# ADC-POWER_SUPPLY_2.net
KiCad netlist of a schematic drawn in Altium Designer
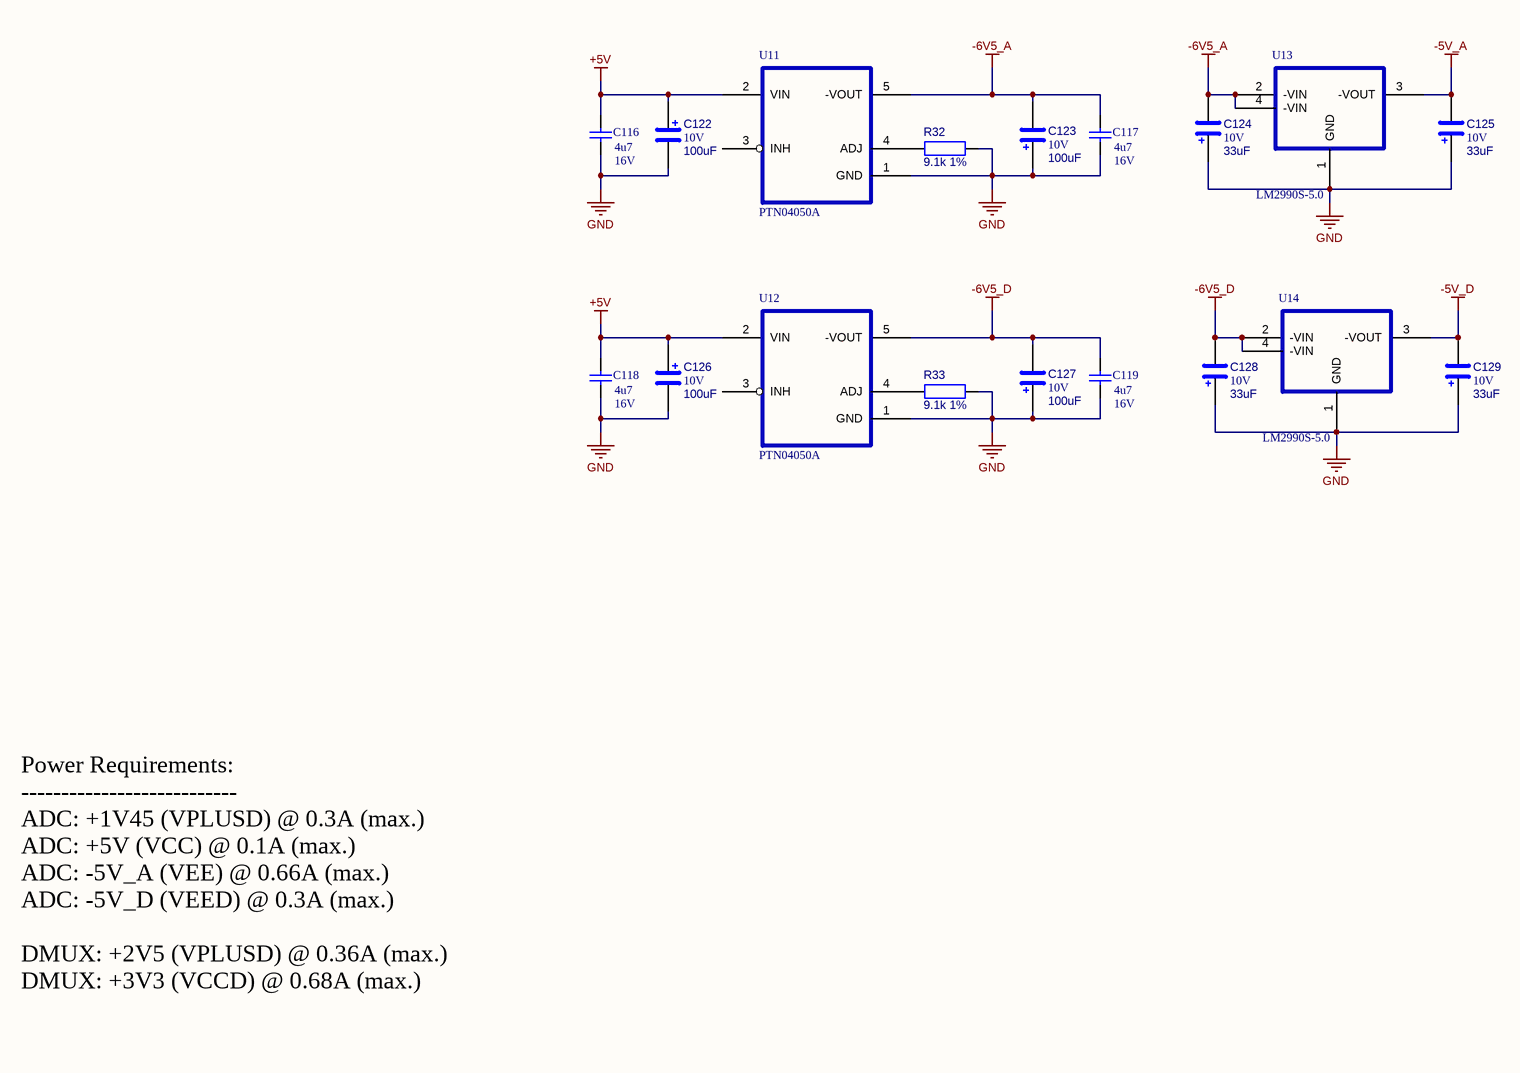
[diagram p0: ADC-POWER SUPPLY 2.SchDoc]

(export (version "E")
  (design (tool "Eeschema 10.0.6"))
  (components
    (comp (ref "C116")
      (value "4u7")
      (footprint "CAPC3225X220N")
      (description "Capacitor 1210 SMD")
      (fields
        (field (name "VOLTAGE") "16V")
        (field (name "CREATED_BY") "EDA-ASA")
        (field (name "CHECKED_BY") "*")
      )
      (libsource (lib "EDA-Passive") (part "cap1210"))
    )
    (comp (ref "C117")
      (value "4u7")
      (footprint "CAPC3225X220N")
      (description "Capacitor 1210 SMD")
      (fields
        (field (name "VOLTAGE") "16V")
        (field (name "CREATED_BY") "EDA-ASA")
        (field (name "CHECKED_BY") "*")
      )
      (libsource (lib "EDA-Passive") (part "cap1210"))
    )
    (comp (ref "C118")
      (value "4u7")
      (footprint "CAPC3225X220N")
      (description "Capacitor 1210 SMD")
      (fields
        (field (name "VOLTAGE") "16V")
        (field (name "CREATED_BY") "EDA-ASA")
        (field (name "CHECKED_BY") "*")
      )
      (libsource (lib "EDA-Passive") (part "cap1210"))
    )
    (comp (ref "C119")
      (value "4u7")
      (footprint "CAPC3225X220N")
      (description "Capacitor 1210 SMD")
      (fields
        (field (name "VOLTAGE") "16V")
        (field (name "CREATED_BY") "EDA-ASA")
        (field (name "CHECKED_BY") "*")
      )
      (libsource (lib "EDA-Passive") (part "cap1210"))
    )
    (comp (ref "C122")
      (value "100uF")
      (footprint "3528")
      (description "CAPACITOR-POLARISED")
      (fields
        (field (name "VOLTAGE") "10V")
        (field (name "CREATED_BY") "EDA-ASA")
        (field (name "CHECKED_BY") "*")
      )
      (libsource (lib "ADC1X2200-10_V1-0") (part "CAPACITOR-POLARISED"))
    )
    (comp (ref "C123")
      (value "100uF")
      (footprint "3528")
      (description "CAPACITOR-POLARISED")
      (fields
        (field (name "VOLTAGE") "10V")
        (field (name "CREATED_BY") "EDA-ASA")
        (field (name "CHECKED_BY") "*")
      )
      (libsource (lib "ADC1X2200-10_V1-0") (part "CAPACITOR-POLARISED"))
    )
    (comp (ref "C124")
      (value "33uF")
      (footprint "3528")
      (description "CAPACITOR-POLARISED")
      (fields
        (field (name "VOLTAGE") "10V")
        (field (name "CREATED_BY") "EDA-ASA")
        (field (name "CHECKED_BY") "*")
      )
      (libsource (lib "ADC1X2200-10_V1-0") (part "CAPACITOR-POLARISED"))
    )
    (comp (ref "C125")
      (value "33uF")
      (footprint "3528")
      (description "CAPACITOR-POLARISED")
      (fields
        (field (name "VOLTAGE") "10V")
        (field (name "CREATED_BY") "EDA-ASA")
        (field (name "CHECKED_BY") "*")
      )
      (libsource (lib "ADC1X2200-10_V1-0") (part "CAPACITOR-POLARISED"))
    )
    (comp (ref "C126")
      (value "100uF")
      (footprint "3528")
      (description "CAPACITOR-POLARISED")
      (fields
        (field (name "VOLTAGE") "10V")
        (field (name "CREATED_BY") "EDA-ASA")
        (field (name "CHECKED_BY") "*")
      )
      (libsource (lib "ADC1X2200-10_V1-0") (part "CAPACITOR-POLARISED"))
    )
    (comp (ref "C127")
      (value "100uF")
      (footprint "3528")
      (description "CAPACITOR-POLARISED")
      (fields
        (field (name "VOLTAGE") "10V")
        (field (name "CREATED_BY") "EDA-ASA")
        (field (name "CHECKED_BY") "*")
      )
      (libsource (lib "ADC1X2200-10_V1-0") (part "CAPACITOR-POLARISED"))
    )
    (comp (ref "C128")
      (value "33uF")
      (footprint "3528")
      (description "CAPACITOR-POLARISED")
      (fields
        (field (name "VOLTAGE") "10V")
        (field (name "CREATED_BY") "EDA-ASA")
        (field (name "CHECKED_BY") "*")
      )
      (libsource (lib "ADC1X2200-10_V1-0") (part "CAPACITOR-POLARISED"))
    )
    (comp (ref "C129")
      (value "33uF")
      (footprint "3528")
      (description "CAPACITOR-POLARISED")
      (fields
        (field (name "VOLTAGE") "10V")
        (field (name "CREATED_BY") "EDA-ASA")
        (field (name "CHECKED_BY") "*")
      )
      (libsource (lib "ADC1X2200-10_V1-0") (part "CAPACITOR-POLARISED"))
    )
    (comp (ref "R32")
      (value "9.1k 1%")
      (footprint "0603")
      (description "RESISTOR SMD 0603")
      (fields (field (name "CREATED_BY") "*") (field (name "CHECKED_BY") "NN"))
      (libsource (lib "EDA_Passive") (part "RES-0805"))
    )
    (comp (ref "R33")
      (value "9.1k 1%")
      (footprint "0603")
      (description "RESISTOR SMD 0603")
      (fields (field (name "CREATED_BY") "*") (field (name "CHECKED_BY") "NN"))
      (libsource (lib "EDA_Passive") (part "RES-0805"))
    )
    (comp (ref "U11")
      (value "PTN04050A")
      (footprint "TI_EUU")
      (libsource (lib "ADC1X2200-10_V1-0") (part "PTN04050A"))
    )
    (comp (ref "U12")
      (value "PTN04050A")
      (footprint "TI_EUU")
      (libsource (lib "ADC1X2200-10_V1-0") (part "PTN04050A"))
    )
    (comp (ref "U13")
      (value "LM2990S-5.0")
      (footprint "TI_TO-263-3")
      (libsource (lib "ADC1X2200-10_V1-1") (part "LM2990S-5.0"))
    )
    (comp (ref "U14")
      (value "LM2990S-5.0")
      (footprint "TI_TO-263-3")
      (libsource (lib "ADC1X2200-10_V1-1") (part "LM2990S-5.0"))
    )
  )
  (nets
    (net (code "1") (name "+5V") (class "Default")
      (node (ref "C116") (pin "2") (pinfunction "2_2") (pintype "passive"))
      (node (ref "C118") (pin "2") (pinfunction "2_2") (pintype "passive"))
      (node (ref "C122") (pin "1") (pinfunction "1_1") (pintype "passive"))
      (node (ref "C126") (pin "1") (pinfunction "1_1") (pintype "passive"))
      (node (ref "U11") (pin "2") (pinfunction "VIN_2") (pintype "power_in"))
      (node (ref "U12") (pin "2") (pinfunction "VIN_2") (pintype "power_in"))
    )
    (net (code "2") (name "-5V_A") (class "Default")
      (node (ref "C125") (pin "2") (pinfunction "2_2") (pintype "passive"))
      (node (ref "U13") (pin "3") (pinfunction "-VOUT_3") (pintype "power_in"))
    )
    (net (code "3") (name "-5V_D") (class "Default")
      (node (ref "C129") (pin "2") (pinfunction "2_2") (pintype "passive"))
      (node (ref "U14") (pin "3") (pinfunction "-VOUT_3") (pintype "power_in"))
    )
    (net (code "4") (name "-6V5_A") (class "Default")
      (node (ref "C117") (pin "2") (pinfunction "2_2") (pintype "passive"))
      (node (ref "C123") (pin "2") (pinfunction "2_2") (pintype "passive"))
      (node (ref "C124") (pin "2") (pinfunction "2_2") (pintype "passive"))
      (node (ref "U11") (pin "5") (pinfunction "-VOUT_5") (pintype "power_in"))
      (node (ref "U13") (pin "2") (pinfunction "-VIN_2") (pintype "power_in"))
      (node (ref "U13") (pin "4") (pinfunction "-VIN_4") (pintype "power_in"))
    )
    (net (code "5") (name "-6V5_D") (class "Default")
      (node (ref "C119") (pin "2") (pinfunction "2_2") (pintype "passive"))
      (node (ref "C127") (pin "2") (pinfunction "2_2") (pintype "passive"))
      (node (ref "C128") (pin "2") (pinfunction "2_2") (pintype "passive"))
      (node (ref "U12") (pin "5") (pinfunction "-VOUT_5") (pintype "power_in"))
      (node (ref "U14") (pin "2") (pinfunction "-VIN_2") (pintype "power_in"))
      (node (ref "U14") (pin "4") (pinfunction "-VIN_4") (pintype "power_in"))
    )
    (net (code "6") (name "GND") (class "Default")
      (node (ref "C116") (pin "1") (pinfunction "1_1") (pintype "passive"))
      (node (ref "C117") (pin "1") (pinfunction "1_1") (pintype "passive"))
      (node (ref "C118") (pin "1") (pinfunction "1_1") (pintype "passive"))
      (node (ref "C119") (pin "1") (pinfunction "1_1") (pintype "passive"))
      (node (ref "C122") (pin "2") (pinfunction "2_2") (pintype "passive"))
      (node (ref "C123") (pin "1") (pinfunction "1_1") (pintype "passive"))
      (node (ref "C124") (pin "1") (pinfunction "1_1") (pintype "passive"))
      (node (ref "C125") (pin "1") (pinfunction "1_1") (pintype "passive"))
      (node (ref "C126") (pin "2") (pinfunction "2_2") (pintype "passive"))
      (node (ref "C127") (pin "1") (pinfunction "1_1") (pintype "passive"))
      (node (ref "C128") (pin "1") (pinfunction "1_1") (pintype "passive"))
      (node (ref "C129") (pin "1") (pinfunction "1_1") (pintype "passive"))
      (node (ref "R32") (pin "2") (pinfunction "2_2") (pintype "passive"))
      (node (ref "R33") (pin "2") (pinfunction "2_2") (pintype "passive"))
      (node (ref "U11") (pin "1") (pinfunction "GND_1") (pintype "power_in"))
      (node (ref "U12") (pin "1") (pinfunction "GND_1") (pintype "power_in"))
      (node (ref "U13") (pin "1") (pinfunction "GND_1") (pintype "power_in"))
      (node (ref "U14") (pin "1") (pinfunction "GND_1") (pintype "power_in"))
    )
    (net (code "7") (name "Net-(U11-ADJ)") (class "Default")
      (node (ref "R32") (pin "1") (pinfunction "1_1") (pintype "passive"))
      (node (ref "U11") (pin "4") (pinfunction "ADJ_4") (pintype "passive"))
    )
    (net (code "8") (name "Net-(U12-ADJ)") (class "Default")
      (node (ref "R33") (pin "1") (pinfunction "1_1") (pintype "passive"))
      (node (ref "U12") (pin "4") (pinfunction "ADJ_4") (pintype "passive"))
    )
    (net (code "9") (name "unconnected-(U11-INH-Pad3)") (class "Default")
      (node (ref "U11") (pin "3") (pinfunction "INH_3") (pintype "passive"))
    )
    (net (code "10") (name "unconnected-(U12-INH-Pad3)") (class "Default")
      (node (ref "U12") (pin "3") (pinfunction "INH_3") (pintype "passive"))
    )
  )
)
